# NUCLEO-F410RB-Wireless.net
KiCad netlist of a schematic drawn in Altium Designer
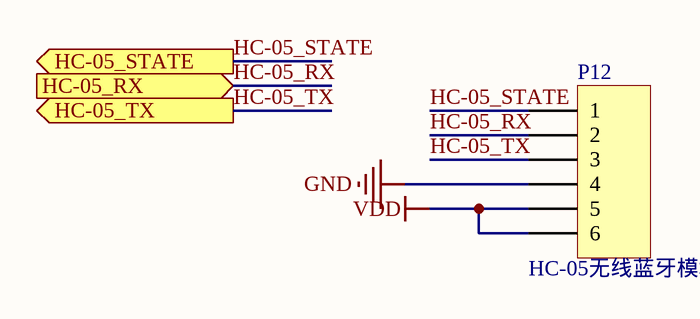
[diagram p0: NUCLEO-F410RB-Wireless.SchDoc]

(export (version "E")
  (design (tool "Eeschema 10.0.6"))
  (components
    (comp (ref "P12")
      (value "HC-05无线蓝牙模块")
      (footprint "HDR1X6")
      (description "Header, 6-Pin")
      (fields (field (name "PUBLISHER") "Altium Limited"))
      (libsource (lib "Connectors") (part "Header 6"))
    )
  )
  (nets
    (net (code "1") (name "/HC-05_RX") (class "Default")
      (node (ref "P12") (pin "2") (pinfunction "2_2") (pintype "passive"))
    )
    (net (code "2") (name "/HC-05_STATE") (class "Default")
      (node (ref "P12") (pin "1") (pinfunction "1_1") (pintype "passive"))
    )
    (net (code "3") (name "/HC-05_TX") (class "Default")
      (node (ref "P12") (pin "3") (pinfunction "3_3") (pintype "passive"))
    )
    (net (code "4") (name "GND") (class "Default")
      (node (ref "P12") (pin "4") (pinfunction "4_4") (pintype "passive"))
    )
    (net (code "5") (name "VDD") (class "Default")
      (node (ref "P12") (pin "5") (pinfunction "5_5") (pintype "passive"))
      (node (ref "P12") (pin "6") (pinfunction "6_6") (pintype "passive"))
    )
  )
)
